# config-bank4.net
KiCad netlist of a schematic drawn in Altium Designer
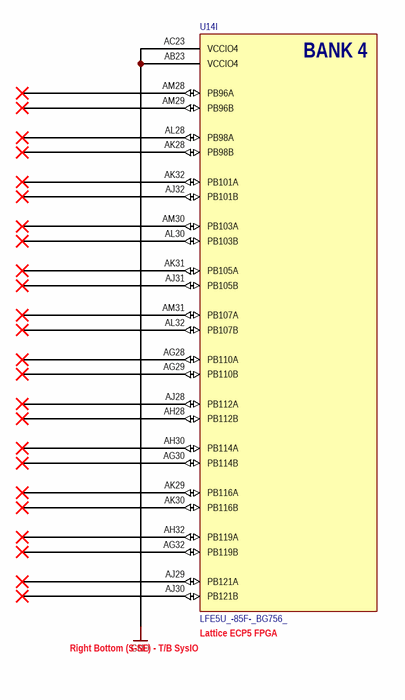
[diagram p0: config-bank4.SchDoc]

(export (version "E")
  (design (tool "Eeschema 10.0.6"))
  (components
    (comp (ref "U14")
      (value "LFE5U_-85F-_BG756_")
      (footprint "lattice:caBGA756")
      (description "ECP5 FPGA, 85k LUT, 756-caBGA")
      (fields (field (name "MANUFACTURER") "Lattice Semiconductor"))
      (libsource (lib "lattice") (part "LFE5U_-85F-_BG756_"))
    )
  )
  (nets
    (net (code "1") (name "GND") (class "Default")
      (node (ref "U14") (pin "AB23") (pinfunction "VCCIO4_AB23") (pintype "power_in"))
      (node (ref "U14") (pin "AC23") (pinfunction "VCCIO4_AC23") (pintype "power_in"))
    )
    (net (code "2") (name "unconnected-(U14I-PB96A-PadAM28)") (class "Default")
      (node (ref "U14") (pin "AM28") (pinfunction "PB96A_AM28") (pintype "bidirectional+no_connect"))
    )
    (net (code "3") (name "unconnected-(U14I-PB96B-PadAM29)") (class "Default")
      (node (ref "U14") (pin "AM29") (pinfunction "PB96B_AM29") (pintype "bidirectional+no_connect"))
    )
    (net (code "4") (name "unconnected-(U14I-PB98A-PadAL28)") (class "Default")
      (node (ref "U14") (pin "AL28") (pinfunction "PB98A_AL28") (pintype "bidirectional+no_connect"))
    )
    (net (code "5") (name "unconnected-(U14I-PB98B-PadAK28)") (class "Default")
      (node (ref "U14") (pin "AK28") (pinfunction "PB98B_AK28") (pintype "bidirectional+no_connect"))
    )
    (net (code "6") (name "unconnected-(U14I-PB101A-PadAK32)") (class "Default")
      (node (ref "U14") (pin "AK32") (pinfunction "PB101A_AK32") (pintype "bidirectional+no_connect"))
    )
    (net (code "7") (name "unconnected-(U14I-PB101B-PadAJ32)") (class "Default")
      (node (ref "U14") (pin "AJ32") (pinfunction "PB101B_AJ32") (pintype "bidirectional+no_connect"))
    )
    (net (code "8") (name "unconnected-(U14I-PB103A-PadAM30)") (class "Default")
      (node (ref "U14") (pin "AM30") (pinfunction "PB103A_AM30") (pintype "bidirectional+no_connect"))
    )
    (net (code "9") (name "unconnected-(U14I-PB103B-PadAL30)") (class "Default")
      (node (ref "U14") (pin "AL30") (pinfunction "PB103B_AL30") (pintype "bidirectional+no_connect"))
    )
    (net (code "10") (name "unconnected-(U14I-PB105A-PadAK31)") (class "Default")
      (node (ref "U14") (pin "AK31") (pinfunction "PB105A_AK31") (pintype "bidirectional+no_connect"))
    )
    (net (code "11") (name "unconnected-(U14I-PB105B-PadAJ31)") (class "Default")
      (node (ref "U14") (pin "AJ31") (pinfunction "PB105B_AJ31") (pintype "bidirectional+no_connect"))
    )
    (net (code "12") (name "unconnected-(U14I-PB107A-PadAM31)") (class "Default")
      (node (ref "U14") (pin "AM31") (pinfunction "PB107A_AM31") (pintype "bidirectional+no_connect"))
    )
    (net (code "13") (name "unconnected-(U14I-PB107B-PadAL32)") (class "Default")
      (node (ref "U14") (pin "AL32") (pinfunction "PB107B_AL32") (pintype "bidirectional+no_connect"))
    )
    (net (code "14") (name "unconnected-(U14I-PB110A-PadAG28)") (class "Default")
      (node (ref "U14") (pin "AG28") (pinfunction "PB110A_AG28") (pintype "bidirectional+no_connect"))
    )
    (net (code "15") (name "unconnected-(U14I-PB110B-PadAG29)") (class "Default")
      (node (ref "U14") (pin "AG29") (pinfunction "PB110B_AG29") (pintype "bidirectional+no_connect"))
    )
    (net (code "16") (name "unconnected-(U14I-PB112A-PadAJ28)") (class "Default")
      (node (ref "U14") (pin "AJ28") (pinfunction "PB112A_AJ28") (pintype "bidirectional+no_connect"))
    )
    (net (code "17") (name "unconnected-(U14I-PB112B-PadAH28)") (class "Default")
      (node (ref "U14") (pin "AH28") (pinfunction "PB112B_AH28") (pintype "bidirectional+no_connect"))
    )
    (net (code "18") (name "unconnected-(U14I-PB114A-PadAH30)") (class "Default")
      (node (ref "U14") (pin "AH30") (pinfunction "PB114A_AH30") (pintype "bidirectional+no_connect"))
    )
    (net (code "19") (name "unconnected-(U14I-PB114B-PadAG30)") (class "Default")
      (node (ref "U14") (pin "AG30") (pinfunction "PB114B_AG30") (pintype "bidirectional+no_connect"))
    )
    (net (code "20") (name "unconnected-(U14I-PB116A-PadAK29)") (class "Default")
      (node (ref "U14") (pin "AK29") (pinfunction "PB116A_AK29") (pintype "bidirectional+no_connect"))
    )
    (net (code "21") (name "unconnected-(U14I-PB116B-PadAK30)") (class "Default")
      (node (ref "U14") (pin "AK30") (pinfunction "PB116B_AK30") (pintype "bidirectional+no_connect"))
    )
    (net (code "22") (name "unconnected-(U14I-PB119A-PadAH32)") (class "Default")
      (node (ref "U14") (pin "AH32") (pinfunction "PB119A_AH32") (pintype "bidirectional+no_connect"))
    )
    (net (code "23") (name "unconnected-(U14I-PB119B-PadAG32)") (class "Default")
      (node (ref "U14") (pin "AG32") (pinfunction "PB119B_AG32") (pintype "bidirectional+no_connect"))
    )
    (net (code "24") (name "unconnected-(U14I-PB121A-PadAJ29)") (class "Default")
      (node (ref "U14") (pin "AJ29") (pinfunction "PB121A_AJ29") (pintype "bidirectional+no_connect"))
    )
    (net (code "25") (name "unconnected-(U14I-PB121B-PadAJ30)") (class "Default")
      (node (ref "U14") (pin "AJ30") (pinfunction "PB121B_AJ30") (pintype "bidirectional+no_connect"))
    )
  )
)
